# Sheet1.net
KiCad netlist of a schematic drawn in Altium Designer
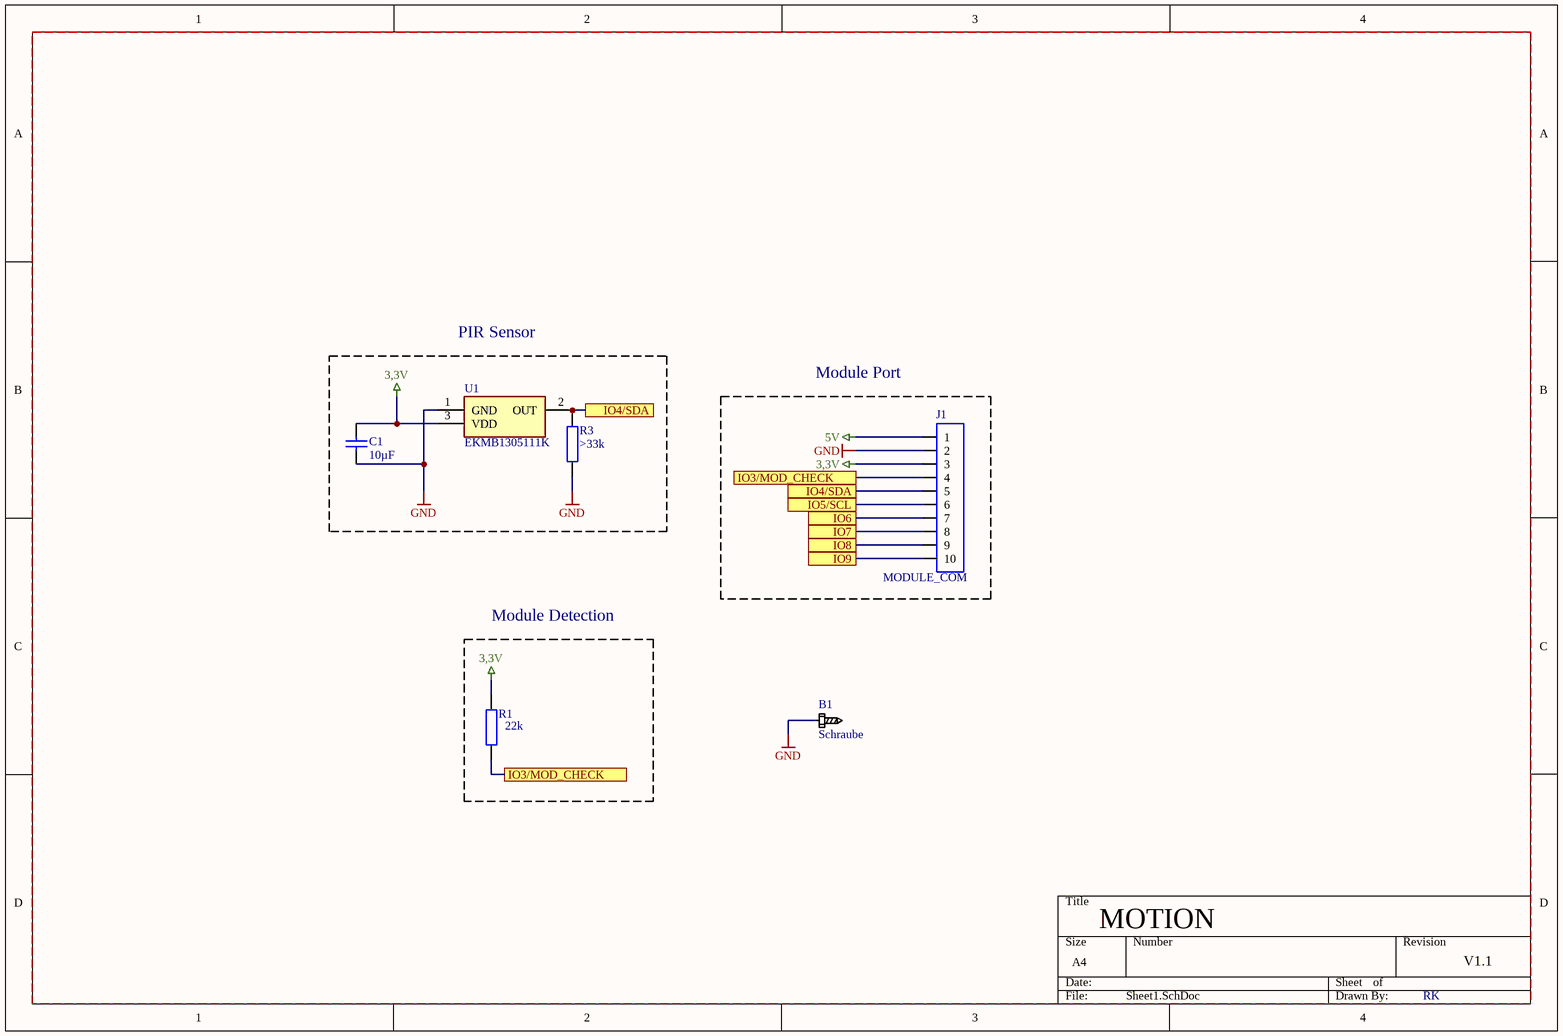
[diagram p0: Sheet1.SchDoc]

(export (version "E")
  (design (tool "Eeschema 10.0.6"))
  (components
    (comp (ref "B1")
      (value "Schraube")
      (footprint "B_Schraube-M3 PAD")
      (description "Schraubenloch für M3 Schrauben")
      (libsource (lib "SCHLIB-PCSB_5.1.3") (part "B_Schraube"))
    )
    (comp (ref "C1")
      (value "10µF")
      (footprint "C_SMD_0603")
      (description "Kondensator SMD Universal, Keramik, Folie, usw.")
      (libsource (lib "SCHLIB-PCSB_5.1.3") (part "C_SMD_KO"))
    )
    (comp (ref "J1")
      (value "MODULE_COM")
      (footprint "SIP-10")
      (description "Stecker")
      (libsource (lib "SCHLIB-PCSB_5.1.3") (part "J_THT_CON10"))
    )
    (comp (ref "R1")
      (value "22k")
      (footprint "R_SMD_0805")
      (description "Widerstand SMD")
      (libsource (lib "SCHLIB-PCSB_5.1.3") (part "R_SMD_Widerstand"))
    )
    (comp (ref "R3")
      (value ">33k")
      (footprint "R_SMD_0805")
      (description "Widerstand SMD")
      (libsource (lib "SCHLIB-PCSB_5.1.3") (part "R_SMD_Widerstand"))
    )
    (comp (ref "U1")
      (value "EKMB1305111K")
      (footprint "SamacSys:EKMB1305111K")
      (description "Undefined or Miscellaneous")
      (fields (field (name "MOUSER PART NUMBER") "667-EKMB1305111K"))
      (libsource (lib "*") (part "EKMB1305111K"))
    )
  )
  (nets
    (net (code "1") (name "/IO3{slash}MOD_CHECK") (class "Default")
      (node (ref "J1") (pin "4") (pinfunction "4_4") (pintype "passive"))
      (node (ref "R1") (pin "1") (pintype "passive"))
    )
    (net (code "2") (name "/IO4{slash}SDA") (class "Default")
      (node (ref "J1") (pin "5") (pinfunction "5_5") (pintype "passive"))
      (node (ref "R3") (pin "2") (pintype "passive"))
      (node (ref "U1") (pin "2") (pinfunction "OUT_2") (pintype "passive"))
    )
    (net (code "3") (name "/IO5{slash}SCL") (class "Default")
      (node (ref "J1") (pin "6") (pinfunction "6_6") (pintype "passive"))
    )
    (net (code "4") (name "/IO6") (class "Default")
      (node (ref "J1") (pin "7") (pinfunction "7_7") (pintype "passive"))
    )
    (net (code "5") (name "/IO7") (class "Default")
      (node (ref "J1") (pin "8") (pinfunction "8_8") (pintype "passive"))
    )
    (net (code "6") (name "/IO8") (class "Default")
      (node (ref "J1") (pin "9") (pinfunction "9_9") (pintype "passive"))
    )
    (net (code "7") (name "/IO9") (class "Default")
      (node (ref "J1") (pin "10") (pinfunction "10_10") (pintype "passive"))
    )
    (net (code "8") (name "3,3V") (class "Default")
      (node (ref "C1") (pin "2") (pintype "passive"))
      (node (ref "J1") (pin "3") (pinfunction "3_3") (pintype "passive"))
      (node (ref "R1") (pin "2") (pintype "passive"))
      (node (ref "U1") (pin "3") (pinfunction "VDD_3") (pintype "passive"))
    )
    (net (code "9") (name "5V") (class "Default")
      (node (ref "J1") (pin "1") (pinfunction "1_1") (pintype "passive"))
    )
    (net (code "10") (name "GND") (class "Default")
      (node (ref "B1") (pin "1") (pinfunction "PAD_1") (pintype "passive"))
      (node (ref "C1") (pin "1") (pintype "passive"))
      (node (ref "J1") (pin "2") (pinfunction "2_2") (pintype "passive"))
      (node (ref "R3") (pin "1") (pintype "passive"))
      (node (ref "U1") (pin "1") (pinfunction "GND_1") (pintype "passive"))
    )
  )
)
